# STM32_microcontroller_IOs.net
KiCad netlist of a schematic drawn in Altium Designer
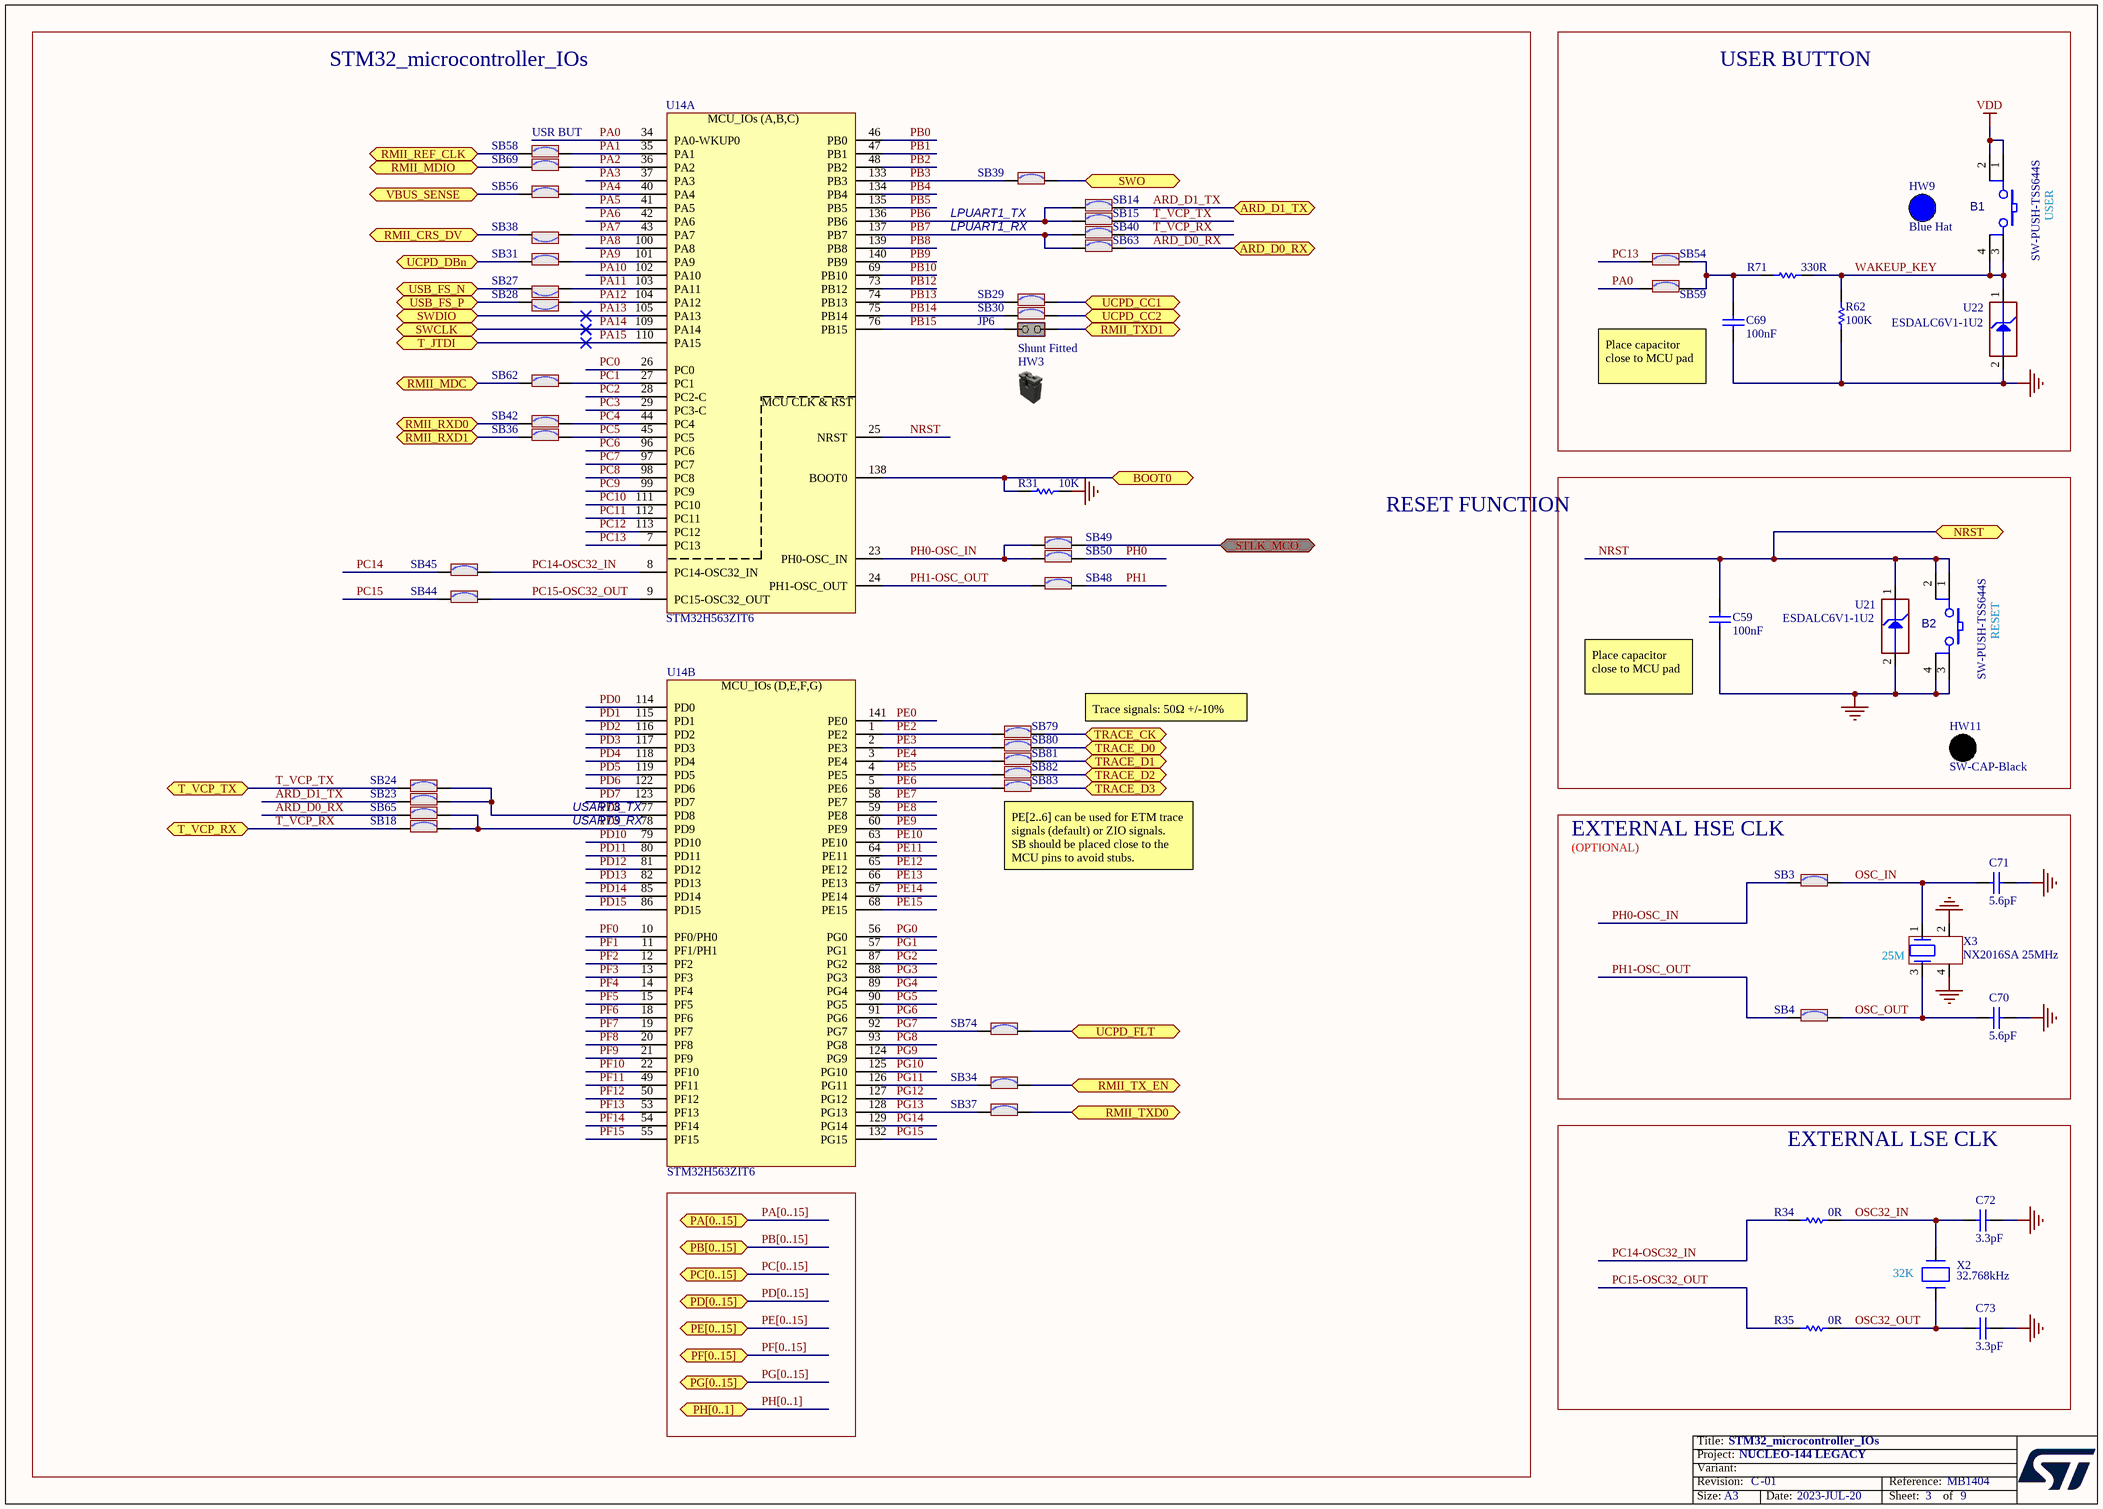
[diagram p0: STM32_microcontroller_IOs.SchDoc]

(export (version "E")
  (design (tool "Eeschema 10.0.6"))
  (components
    (comp (ref "B1")
      (value "SW-PUSH-TSS644S")
      (footprint "MCD_PARTS:SWI_KNITTER_TSS644S")
      (description "Push Button, NO, 0.05A, 12V, 2.6N, SMD, 9.0x6.2mm, T=7.3mm, changeable caps KTSC-6xx")
      (fields
        (field (name "INTERNAL_PART_NUMBER") "MCD-02417")
        (field (name "MANUFACTURER") "KNITTER-SWITCH")
      )
      (libsource (lib "MCD_PARTS_database") (part "SW_PUSH_SMD"))
    )
    (comp (ref "B2")
      (value "SW-PUSH-TSS644S")
      (footprint "MCD_PARTS:SWI_KNITTER_TSS644S")
      (description "Push Button, NO, 0.05A, 12V, 2.6N, SMD, 9.0x6.2mm, T=7.3mm, changeable caps KTSC-6xx")
      (fields
        (field (name "INTERNAL_PART_NUMBER") "MCD-02417")
        (field (name "MANUFACTURER") "KNITTER-SWITCH")
      )
      (libsource (lib "MCD_PARTS_database") (part "SW_PUSH_SMD"))
    )
    (comp (ref "C59")
      (value "100nF")
      (footprint "C0603")
      (description "Capacitor, MLCC, 100nF, 6V3, X5R, +/-10%, 0603, T=0.8mm")
      (fields (field (name "INTERNAL_PART_NUMBER") "MCD-02119") (field (name "MANUFACTURER") "KEMET"))
      (libsource (lib "MCD_PARTS_database") (part "Capacitor"))
    )
    (comp (ref "C69")
      (value "100nF")
      (footprint "C0603")
      (description "Capacitor, MLCC, 100nF, 6V3, X5R, +/-10%, 0603, T=0.8mm")
      (fields (field (name "INTERNAL_PART_NUMBER") "MCD-02119") (field (name "MANUFACTURER") "KEMET"))
      (libsource (lib "MCD_PARTS_database") (part "Capacitor"))
    )
    (comp (ref "C70")
      (value "5.6pF")
      (footprint "MCD_PARTS:C0402")
      (description "Capacitor, MLCC, 5.6pF, 50V, NPO, 5%, 0402, T=0,5mm")
      (fields
        (field (name "INTERNAL_PART_NUMBER") "MCD-01374")
        (field (name "MANUFACTURER_PART_NUMBER") "CC0402BRNPO9BN5R6")
        (field (name "PROVIDED_BY") "SUBCO")
      )
      (libsource (lib "MCD_PARTS_database") (part "Capacitor"))
    )
    (comp (ref "C71")
      (value "5.6pF")
      (footprint "MCD_PARTS:C0402")
      (description "Capacitor, MLCC, 5.6pF, 50V, NPO, 5%, 0402, T=0,5mm")
      (fields
        (field (name "INTERNAL_PART_NUMBER") "MCD-01374")
        (field (name "MANUFACTURER_PART_NUMBER") "CC0402BRNPO9BN5R6")
        (field (name "PROVIDED_BY") "SUBCO")
      )
      (libsource (lib "MCD_PARTS_database") (part "Capacitor"))
    )
    (comp (ref "C72")
      (value "3.3pF")
      (footprint "MCD_PARTS:C0402")
      (description "Capacitor, MLCC, 3.3pF, 50V, NPO, +/-0.1pF, 0402, T=0.5mm")
      (fields (field (name "INTERNAL_PART_NUMBER") "MCD-01775") (field (name "MANUFACTURER") "YAGEO"))
      (libsource (lib "MCD_PARTS_database") (part "Capacitor"))
    )
    (comp (ref "C73")
      (value "3.3pF")
      (footprint "MCD_PARTS:C0402")
      (description "Capacitor, MLCC, 3.3pF, 50V, NPO, +/-0.1pF, 0402, T=0.5mm")
      (fields (field (name "INTERNAL_PART_NUMBER") "MCD-01775") (field (name "MANUFACTURER") "YAGEO"))
      (libsource (lib "MCD_PARTS_database") (part "Capacitor"))
    )
    (comp (ref "HW3")
      (value "Shunt Black 2.54mm")
      (description "SHUNT 2.54mm BLACK")
      (fields
        (field (name "INTERNAL_PART_NUMBER") "MCD-00043")
        (field (name "MANUFACTURER_PART_NUMBER") "SNT-100-BK-G")
        (field (name "PROVIDED_BY") "SUBCO")
      )
      (libsource (lib "MCD_PARTS_database") (part "Shunt Black 2.54mm"))
    )
    (comp (ref "HW9")
      (value "Blue Hat")
      (description "Switch hat, blue, For KTSC-62B")
      (fields (field (name "INTERNAL_PART_NUMBER") "MCD-02136") (field (name "MANUFACTURER") "APEM INC"))
      (libsource (lib "MCD_PARTS_database") (part "BUTTON_HAT_BLUE"))
    )
    (comp (ref "HW11")
      (value "SW-CAP-Black")
      (description "Black round cap for TSS6x series")
      (fields
        (field (name "INTERNAL_PART_NUMBER") "MCD-02420")
        (field (name "MANUFACTURER") "KNITTER-SWITCH")
      )
      (libsource (lib "MCD_PARTS_database") (part "SW-CAP-Black"))
    )
    (comp (ref "JP6")
      (value "Shunt Fitted")
      (footprint "MCD_PARTS:CON_SAMTEC_TSW-102-07-G-S")
      (description "Header, 2x1, 2,54mm, VR, TH, Height 5.84mm/2.54mm - Shunt Fitted by default")
      (fields
        (field (name "INTERNAL_PART_NUMBER") "MCD-00683")
        (field (name "MANUFACTURER_PART_NUMBER") "TSW-102-07-x-S")
        (field (name "PROVIDED_BY") "SUBCO")
      )
      (libsource (lib "MCD_PARTS_database") (part "Jumper_Header 2x1 Fitted"))
    )
    (comp (ref "R31")
      (value "10K")
      (footprint "MCD_PARTS:R0603")
      (description "Resistor,10K,0603,1%,1/10W")
      (fields
        (field (name "INTERNAL_PART_NUMBER") "MCD-00220")
        (field (name "MANUFACTURER_PART_NUMBER") "RC0603FR-0710KL")
        (field (name "PROVIDED_BY") "SUBCO")
      )
      (libsource (lib "MCD_PARTS_database") (part "Resistor"))
    )
    (comp (ref "R34")
      (value "0R")
      (footprint "MCD_PARTS:R0603")
      (description "Resistor,0R,0603,5%,1/10W")
      (fields
        (field (name "INTERNAL_PART_NUMBER") "MCD-00056")
        (field (name "MANUFACTURER_PART_NUMBER") "RC0603JR-070RL")
        (field (name "PROVIDED_BY") "SUBCO")
      )
      (libsource (lib "MCD_PARTS_database") (part "Resistor"))
    )
    (comp (ref "R35")
      (value "0R")
      (footprint "MCD_PARTS:R0603")
      (description "Resistor,0R,0603,5%,1/10W")
      (fields
        (field (name "INTERNAL_PART_NUMBER") "MCD-00056")
        (field (name "MANUFACTURER_PART_NUMBER") "RC0603JR-070RL")
        (field (name "PROVIDED_BY") "SUBCO")
      )
      (libsource (lib "MCD_PARTS_database") (part "Resistor"))
    )
    (comp (ref "R62")
      (value "100K")
      (footprint "MCD_PARTS:R0603")
      (description "Resistor,100K,0603,1%,1/10W")
      (fields
        (field (name "INTERNAL_PART_NUMBER") "MCD-00223")
        (field (name "MANUFACTURER_PART_NUMBER") "RC0603FR-07100KL")
        (field (name "PROVIDED_BY") "SUBCO")
      )
      (libsource (lib "MCD_PARTS_database") (part "Resistor"))
    )
    (comp (ref "R71")
      (value "330R")
      (footprint "MCD_PARTS:R0603")
      (description "Resistor,330R,0603,1%,1/10W")
      (fields
        (field (name "INTERNAL_PART_NUMBER") "MCD-00197")
        (field (name "MANUFACTURER_PART_NUMBER") "RC0603FR-07330RL")
        (field (name "PROVIDED_BY") "SUBCO")
      )
      (libsource (lib "MCD_PARTS_database") (part "Resistor"))
    )
    (comp (ref "SB3")
      (value "SB_ON")
      (footprint "MCD_PARTS:SOLDER-BRIDGE_R0603-0R")
      (description "Solder Bridge ON")
      (fields
        (field (name "INTERNAL_PART_NUMBER") "MCD-00071")
        (field (name "MANUFACTURER_PART_NUMBER") "RC0603JR-070RL")
        (field (name "PROVIDED_BY") "SUBCO")
      )
      (libsource (lib "MCD_PARTS_database") (part "SB_ON"))
    )
    (comp (ref "SB4")
      (value "SB_ON")
      (footprint "MCD_PARTS:SOLDER-BRIDGE_R0603-0R")
      (description "Solder Bridge ON")
      (fields
        (field (name "INTERNAL_PART_NUMBER") "MCD-00071")
        (field (name "MANUFACTURER_PART_NUMBER") "RC0603JR-070RL")
        (field (name "PROVIDED_BY") "SUBCO")
      )
      (libsource (lib "MCD_PARTS_database") (part "SB_ON"))
    )
    (comp (ref "SB14")
      (value "SB_ON")
      (footprint "MCD_PARTS:SOLDER-BRIDGE_R0603-0R")
      (description "Solder Bridge ON")
      (fields
        (field (name "INTERNAL_PART_NUMBER") "MCD-00071")
        (field (name "MANUFACTURER_PART_NUMBER") "RC0603JR-070RL")
        (field (name "PROVIDED_BY") "SUBCO")
      )
      (libsource (lib "") (part "SB_ON_1"))
    )
    (comp (ref "SB15")
      (value "SB_ON")
      (footprint "MCD_PARTS:SOLDER-BRIDGE_R0603-0R")
      (description "Solder Bridge ON")
      (fields
        (field (name "INTERNAL_PART_NUMBER") "MCD-00071")
        (field (name "MANUFACTURER_PART_NUMBER") "RC0603JR-070RL")
        (field (name "PROVIDED_BY") "SUBCO")
      )
      (libsource (lib "") (part "SB_ON_1"))
    )
    (comp (ref "SB18")
      (value "SB_ON")
      (footprint "MCD_PARTS:SOLDER-BRIDGE_R0603-0R")
      (description "Solder Bridge ON")
      (fields
        (field (name "INTERNAL_PART_NUMBER") "MCD-00071")
        (field (name "MANUFACTURER_PART_NUMBER") "RC0603JR-070RL")
        (field (name "PROVIDED_BY") "SUBCO")
      )
      (libsource (lib "") (part "SB_ON_1"))
    )
    (comp (ref "SB23")
      (value "SB_ON")
      (footprint "MCD_PARTS:SOLDER-BRIDGE_R0603-0R")
      (description "Solder Bridge ON")
      (fields
        (field (name "INTERNAL_PART_NUMBER") "MCD-00071")
        (field (name "MANUFACTURER_PART_NUMBER") "RC0603JR-070RL")
        (field (name "PROVIDED_BY") "SUBCO")
      )
      (libsource (lib "") (part "SB_ON_1"))
    )
    (comp (ref "SB24")
      (value "SB_ON")
      (footprint "MCD_PARTS:SOLDER-BRIDGE_R0603-0R")
      (description "Solder Bridge ON")
      (fields
        (field (name "INTERNAL_PART_NUMBER") "MCD-00071")
        (field (name "MANUFACTURER_PART_NUMBER") "RC0603JR-070RL")
        (field (name "PROVIDED_BY") "SUBCO")
      )
      (libsource (lib "") (part "SB_ON_1"))
    )
    (comp (ref "SB27")
      (value "SB_ON")
      (footprint "MCD_PARTS:SOLDER-BRIDGE_R0402-0R")
      (description "Solder Bridge 0402 ON")
      (fields
        (field (name "INTERNAL_PART_NUMBER") "MCD-01618")
        (field (name "MANUFACTURER_PART_NUMBER") "RC0402JR-070RL")
        (field (name "PROVIDED_BY") "SUBCO")
      )
      (libsource (lib "") (part "SB_ON_2"))
    )
    (comp (ref "SB28")
      (value "SB_ON")
      (footprint "MCD_PARTS:SOLDER-BRIDGE_R0402-0R")
      (description "Solder Bridge 0402 ON")
      (fields
        (field (name "INTERNAL_PART_NUMBER") "MCD-01618")
        (field (name "MANUFACTURER_PART_NUMBER") "RC0402JR-070RL")
        (field (name "PROVIDED_BY") "SUBCO")
      )
      (libsource (lib "") (part "SB_ON_2"))
    )
    (comp (ref "SB29")
      (value "SB_ON")
      (footprint "MCD_PARTS:SOLDER-BRIDGE_R0603-0R")
      (description "Solder Bridge ON")
      (fields
        (field (name "INTERNAL_PART_NUMBER") "MCD-00071")
        (field (name "MANUFACTURER_PART_NUMBER") "RC0603JR-070RL")
        (field (name "PROVIDED_BY") "SUBCO")
      )
      (libsource (lib "MCD_PARTS_database") (part "SB_ON"))
    )
    (comp (ref "SB30")
      (value "SB_ON")
      (footprint "MCD_PARTS:SOLDER-BRIDGE_R0603-0R")
      (description "Solder Bridge ON")
      (fields
        (field (name "INTERNAL_PART_NUMBER") "MCD-00071")
        (field (name "MANUFACTURER_PART_NUMBER") "RC0603JR-070RL")
        (field (name "PROVIDED_BY") "SUBCO")
      )
      (libsource (lib "MCD_PARTS_database") (part "SB_ON"))
    )
    (comp (ref "SB31")
      (value "SB_ON")
      (footprint "MCD_PARTS:SOLDER-BRIDGE_R0402-0R")
      (description "Solder Bridge 0402 ON")
      (fields
        (field (name "INTERNAL_PART_NUMBER") "MCD-01618")
        (field (name "MANUFACTURER_PART_NUMBER") "RC0402JR-070RL")
        (field (name "PROVIDED_BY") "SUBCO")
      )
      (libsource (lib "MCD_PARTS_database") (part "SB_ON"))
    )
    (comp (ref "SB34")
      (value "SB_ON")
      (footprint "MCD_PARTS:SOLDER-BRIDGE_R0603-0R")
      (description "Solder Bridge ON")
      (fields
        (field (name "INTERNAL_PART_NUMBER") "MCD-00071")
        (field (name "MANUFACTURER_PART_NUMBER") "RC0603JR-070RL")
        (field (name "PROVIDED_BY") "SUBCO")
      )
      (libsource (lib "") (part "SB_ON_1"))
    )
    (comp (ref "SB36")
      (value "SB_ON")
      (footprint "MCD_PARTS:SOLDER-BRIDGE_R0402-0R")
      (description "Solder Bridge 0402 ON")
      (fields
        (field (name "INTERNAL_PART_NUMBER") "MCD-01618")
        (field (name "MANUFACTURER_PART_NUMBER") "RC0402JR-070RL")
        (field (name "PROVIDED_BY") "SUBCO")
      )
      (libsource (lib "MCD_PARTS_database") (part "SB_ON"))
    )
    (comp (ref "SB37")
      (value "SB_ON")
      (footprint "MCD_PARTS:SOLDER-BRIDGE_R0603-0R")
      (description "Solder Bridge ON")
      (fields
        (field (name "INTERNAL_PART_NUMBER") "MCD-00071")
        (field (name "MANUFACTURER_PART_NUMBER") "RC0603JR-070RL")
        (field (name "PROVIDED_BY") "SUBCO")
      )
      (libsource (lib "") (part "SB_ON_1"))
    )
    (comp (ref "SB38")
      (value "SB_ON")
      (footprint "MCD_PARTS:SOLDER-BRIDGE_R0402-0R")
      (description "Solder Bridge 0402 ON")
      (fields
        (field (name "INTERNAL_PART_NUMBER") "MCD-01618")
        (field (name "MANUFACTURER_PART_NUMBER") "RC0402JR-070RL")
        (field (name "PROVIDED_BY") "SUBCO")
      )
      (libsource (lib "") (part "SB_ON_2"))
    )
    (comp (ref "SB39")
      (value "SB_ON")
      (footprint "MCD_PARTS:SOLDER-BRIDGE_R0603-0R")
      (description "Solder Bridge ON")
      (fields
        (field (name "INTERNAL_PART_NUMBER") "MCD-00071")
        (field (name "MANUFACTURER_PART_NUMBER") "RC0603JR-070RL")
        (field (name "PROVIDED_BY") "SUBCO")
      )
      (libsource (lib "") (part "SB_ON_1"))
    )
    (comp (ref "SB40")
      (value "SB_ON")
      (footprint "MCD_PARTS:SOLDER-BRIDGE_R0603-0R")
      (description "Solder Bridge ON")
      (fields
        (field (name "INTERNAL_PART_NUMBER") "MCD-00071")
        (field (name "MANUFACTURER_PART_NUMBER") "RC0603JR-070RL")
        (field (name "PROVIDED_BY") "SUBCO")
      )
      (libsource (lib "") (part "SB_ON_1"))
    )
    (comp (ref "SB42")
      (value "SB_ON")
      (footprint "MCD_PARTS:SOLDER-BRIDGE_R0603-0R")
      (description "Solder Bridge ON")
      (fields
        (field (name "INTERNAL_PART_NUMBER") "MCD-00071")
        (field (name "MANUFACTURER_PART_NUMBER") "RC0603JR-070RL")
        (field (name "PROVIDED_BY") "SUBCO")
      )
      (libsource (lib "MCD_PARTS_database") (part "SB_ON"))
    )
    (comp (ref "SB44")
      (value "SB_ON")
      (footprint "MCD_PARTS:SOLDER-BRIDGE_R0402-0R")
      (description "Solder Bridge 0402 ON")
      (fields
        (field (name "INTERNAL_PART_NUMBER") "MCD-01618")
        (field (name "MANUFACTURER_PART_NUMBER") "RC0402JR-070RL")
        (field (name "PROVIDED_BY") "SUBCO")
      )
      (libsource (lib "MCD_PARTS_database") (part "SB_ON"))
    )
    (comp (ref "SB45")
      (value "SB_ON")
      (footprint "MCD_PARTS:SOLDER-BRIDGE_R0402-0R")
      (description "Solder Bridge 0402 ON")
      (fields
        (field (name "INTERNAL_PART_NUMBER") "MCD-01618")
        (field (name "MANUFACTURER_PART_NUMBER") "RC0402JR-070RL")
        (field (name "PROVIDED_BY") "SUBCO")
      )
      (libsource (lib "MCD_PARTS_database") (part "SB_ON"))
    )
    (comp (ref "SB48")
      (value "SB_ON")
      (footprint "MCD_PARTS:SOLDER-BRIDGE_R0603-0R")
      (description "Solder Bridge ON")
      (fields
        (field (name "INTERNAL_PART_NUMBER") "MCD-00071")
        (field (name "MANUFACTURER_PART_NUMBER") "RC0603JR-070RL")
        (field (name "PROVIDED_BY") "SUBCO")
      )
      (libsource (lib "MCD_PARTS_database") (part "SB_ON"))
    )
    (comp (ref "SB49")
      (value "SB_ON")
      (footprint "MCD_PARTS:SOLDER-BRIDGE_R0603-0R")
      (description "Solder Bridge ON")
      (fields
        (field (name "INTERNAL_PART_NUMBER") "MCD-00071")
        (field (name "MANUFACTURER_PART_NUMBER") "RC0603JR-070RL")
        (field (name "PROVIDED_BY") "SUBCO")
      )
      (libsource (lib "MCD_PARTS_database") (part "SB_ON"))
    )
    (comp (ref "SB50")
      (value "SB_ON")
      (footprint "MCD_PARTS:SOLDER-BRIDGE_R0603-0R")
      (description "Solder Bridge ON")
      (fields
        (field (name "INTERNAL_PART_NUMBER") "MCD-00071")
        (field (name "MANUFACTURER_PART_NUMBER") "RC0603JR-070RL")
        (field (name "PROVIDED_BY") "SUBCO")
      )
      (libsource (lib "MCD_PARTS_database") (part "SB_ON"))
    )
    (comp (ref "SB54")
      (value "SB_ON")
      (footprint "MCD_PARTS:SOLDER-BRIDGE_R0402-0R")
      (description "Solder Bridge 0402 ON")
      (fields
        (field (name "INTERNAL_PART_NUMBER") "MCD-01618")
        (field (name "MANUFACTURER_PART_NUMBER") "RC0402JR-070RL")
        (field (name "PROVIDED_BY") "SUBCO")
      )
      (libsource (lib "MCD_PARTS_database") (part "SB_ON"))
    )
    (comp (ref "SB56")
      (value "SB_ON")
      (footprint "MCD_PARTS:SOLDER-BRIDGE_R0402-0R")
      (description "Solder Bridge 0402 ON")
      (fields
        (field (name "INTERNAL_PART_NUMBER") "MCD-01618")
        (field (name "MANUFACTURER_PART_NUMBER") "RC0402JR-070RL")
        (field (name "PROVIDED_BY") "SUBCO")
      )
      (libsource (lib "MCD_PARTS_database") (part "SB_ON"))
    )
    (comp (ref "SB58")
      (value "SB_ON")
      (footprint "MCD_PARTS:SOLDER-BRIDGE_R0603-0R")
      (description "Solder Bridge ON")
      (fields
        (field (name "INTERNAL_PART_NUMBER") "MCD-00071")
        (field (name "MANUFACTURER_PART_NUMBER") "RC0603JR-070RL")
        (field (name "PROVIDED_BY") "SUBCO")
      )
      (libsource (lib "") (part "SB_ON_1"))
    )
    (comp (ref "SB59")
      (value "SB_ON")
      (footprint "MCD_PARTS:SOLDER-BRIDGE_R0603-0R")
      (description "Solder Bridge ON")
      (fields
        (field (name "INTERNAL_PART_NUMBER") "MCD-00071")
        (field (name "MANUFACTURER_PART_NUMBER") "RC0603JR-070RL")
        (field (name "PROVIDED_BY") "SUBCO")
      )
      (libsource (lib "") (part "SB_ON_1"))
    )
    (comp (ref "SB62")
      (value "SB_ON")
      (footprint "MCD_PARTS:SOLDER-BRIDGE_R0603-0R")
      (description "Solder Bridge ON")
      (fields
        (field (name "INTERNAL_PART_NUMBER") "MCD-00071")
        (field (name "MANUFACTURER_PART_NUMBER") "RC0603JR-070RL")
        (field (name "PROVIDED_BY") "SUBCO")
      )
      (libsource (lib "MCD_PARTS_database") (part "SB_ON"))
    )
    (comp (ref "SB63")
      (value "SB_ON")
      (footprint "MCD_PARTS:SOLDER-BRIDGE_R0402-0R")
      (description "Solder Bridge 0402 ON")
      (fields
        (field (name "INTERNAL_PART_NUMBER") "MCD-01618")
        (field (name "MANUFACTURER_PART_NUMBER") "RC0402JR-070RL")
        (field (name "PROVIDED_BY") "SUBCO")
      )
      (libsource (lib "MCD_PARTS_database") (part "SB_ON"))
    )
    (comp (ref "SB65")
      (value "SB_ON")
      (footprint "MCD_PARTS:SOLDER-BRIDGE_R0402-0R")
      (description "Solder Bridge 0402 ON")
      (fields
        (field (name "INTERNAL_PART_NUMBER") "MCD-01618")
        (field (name "MANUFACTURER_PART_NUMBER") "RC0402JR-070RL")
        (field (name "PROVIDED_BY") "SUBCO")
      )
      (libsource (lib "MCD_PARTS_database") (part "SB_ON"))
    )
    (comp (ref "SB69")
      (value "SB_ON")
      (footprint "MCD_PARTS:SOLDER-BRIDGE_R0603-0R")
      (description "Solder Bridge ON")
      (fields
        (field (name "INTERNAL_PART_NUMBER") "MCD-00071")
        (field (name "MANUFACTURER_PART_NUMBER") "RC0603JR-070RL")
        (field (name "PROVIDED_BY") "SUBCO")
      )
      (libsource (lib "") (part "SB_ON_1"))
    )
    (comp (ref "SB74")
      (value "SB_ON")
      (footprint "MCD_PARTS:SOLDER-BRIDGE_R0603-0R")
      (description "Solder Bridge ON")
      (fields
        (field (name "INTERNAL_PART_NUMBER") "MCD-00071")
        (field (name "MANUFACTURER_PART_NUMBER") "RC0603JR-070RL")
        (field (name "PROVIDED_BY") "SUBCO")
      )
      (libsource (lib "") (part "SB_ON_1"))
    )
    (comp (ref "SB79")
      (value "SB_ON")
      (footprint "MCD_PARTS:SOLDER-BRIDGE_R0402-0R")
      (description "Solder Bridge 0402 ON")
      (fields
        (field (name "INTERNAL_PART_NUMBER") "MCD-01618")
        (field (name "MANUFACTURER_PART_NUMBER") "RC0402JR-070RL")
        (field (name "PROVIDED_BY") "SUBCO")
      )
      (libsource (lib "MCD_PARTS_database") (part "SB_ON"))
    )
    (comp (ref "SB80")
      (value "SB_ON")
      (footprint "MCD_PARTS:SOLDER-BRIDGE_R0402-0R")
      (description "Solder Bridge 0402 ON")
      (fields
        (field (name "INTERNAL_PART_NUMBER") "MCD-01618")
        (field (name "MANUFACTURER_PART_NUMBER") "RC0402JR-070RL")
        (field (name "PROVIDED_BY") "SUBCO")
      )
      (libsource (lib "MCD_PARTS_database") (part "SB_ON"))
    )
    (comp (ref "SB81")
      (value "SB_ON")
      (footprint "MCD_PARTS:SOLDER-BRIDGE_R0402-0R")
      (description "Solder Bridge 0402 ON")
      (fields
        (field (name "INTERNAL_PART_NUMBER") "MCD-01618")
        (field (name "MANUFACTURER_PART_NUMBER") "RC0402JR-070RL")
        (field (name "PROVIDED_BY") "SUBCO")
      )
      (libsource (lib "MCD_PARTS_database") (part "SB_ON"))
    )
    (comp (ref "SB82")
      (value "SB_ON")
      (footprint "MCD_PARTS:SOLDER-BRIDGE_R0402-0R")
      (description "Solder Bridge 0402 ON")
      (fields
        (field (name "INTERNAL_PART_NUMBER") "MCD-01618")
        (field (name "MANUFACTURER_PART_NUMBER") "RC0402JR-070RL")
        (field (name "PROVIDED_BY") "SUBCO")
      )
      (libsource (lib "MCD_PARTS_database") (part "SB_ON"))
    )
    (comp (ref "SB83")
      (value "SB_ON")
      (footprint "MCD_PARTS:SOLDER-BRIDGE_R0402-0R")
      (description "Solder Bridge 0402 ON")
      (fields
        (field (name "INTERNAL_PART_NUMBER") "MCD-01618")
        (field (name "MANUFACTURER_PART_NUMBER") "RC0402JR-070RL")
        (field (name "PROVIDED_BY") "SUBCO")
      )
      (libsource (lib "MCD_PARTS_database") (part "SB_ON"))
    )
    (comp (ref "U14")
      (value "STM32H563ZIT6")
      (footprint "MCD_PARTS:ICC_LQFP144_20X20_P050_SOCKET_YAMAICHI_IC149-144-145-B5_NM")
      (description "STM32H563ZIT6, LQFP144 package, 20x20")
      (fields
        (field (name "INTERNAL_PART_NUMBER") "MCD-02359")
        (field (name "MANUFACTURER") "STMICROELECTRONICS")
      )
      (libsource (lib "MCD_PARTS_database") (part "STM32H563ZIT6"))
    )
    (comp (ref "U21")
      (value "ESDALC6V1-1U2")
      (footprint "MCD_PARTS:ESD_ST0201")
      (description "ESD protection 6V1")
      (fields
        (field (name "INTERNAL_PART_NUMBER") "MCD-00170")
        (field (name "MANUFACTURER") "STMICROELECTRONICS")
        (field (name "PROVIDED_BY") "SUBCO with ST control")
      )
      (libsource (lib "MCD_PARTS_database") (part "ESD-TRANSIL"))
    )
    (comp (ref "U22")
      (value "ESDALC6V1-1U2")
      (footprint "MCD_PARTS:ESD_ST0201")
      (description "ESD protection 6V1")
      (fields
        (field (name "INTERNAL_PART_NUMBER") "MCD-00170")
        (field (name "MANUFACTURER") "STMICROELECTRONICS")
        (field (name "PROVIDED_BY") "SUBCO with ST control")
      )
      (libsource (lib "MCD_PARTS_database") (part "ESD-TRANSIL"))
    )
    (comp (ref "X2")
      (value "32.768kHz")
      (footprint "MCD_PARTS:CRY_NX1610SE_2P")
      (description "Crystal, 32.768kHz, 9pF, +/-20ppm, 70KR, 1.6x1mm")
      (fields (field (name "INTERNAL_PART_NUMBER") "MCD-02291") (field (name "MANUFACTURER") "NDK"))
      (libsource (lib "MCD_PARTS_database") (part "XTAL_2_PINS"))
    )
    (comp (ref "X3")
      (value "NX2016SA 25MHz")
      (footprint "MCD_PARTS:CRY_NX2016SA_4P")
      (description "Crystal 25MHz, 6pF, +-20ppm, 80ohms max, SMD")
      (fields
        (field (name "INTERNAL_PART_NUMBER") "MCD-01364")
        (field (name "MANUFACTURER_PART_NUMBER") "NX2016SA 25MHz EXS00A-CS11321")
        (field (name "PROVIDED_BY") "SUBCO")
      )
      (libsource (lib "MCD_PARTS_database") (part "XTAL_4_PINS"))
    )
  )
  (nets
    (net (code "3") (name "/ARD_D0_RX") (class "Default")
      (node (ref "SB63") (pin "2") (pinfunction "2_2") (pintype "passive"))
      (node (ref "SB65") (pin "1") (pinfunction "1_1") (pintype "passive"))
    )
    (net (code "4") (name "/ARD_D1_TX") (class "Default")
      (node (ref "SB14") (pin "1") (pinfunction "1_1") (pintype "passive"))
      (node (ref "SB23") (pin "2") (pinfunction "2_2") (pintype "passive"))
    )
    (net (code "5") (name "/BOOT0") (class "Default")
      (node (ref "R31") (pin "1") (pinfunction "1_1") (pintype "passive"))
      (node (ref "U14") (pin "138") (pinfunction "BOOT0_138") (pintype "passive"))
    )
    (net (code "6") (name "/NRST") (class "Default")
      (node (ref "B2") (pin "1") (pinfunction "1_1") (pintype "passive"))
      (node (ref "B2") (pin "2") (pinfunction "2_2") (pintype "passive"))
      (node (ref "C59") (pin "2") (pinfunction "2_2") (pintype "passive"))
      (node (ref "U14") (pin "25") (pinfunction "NRST_25") (pintype "passive"))
      (node (ref "U21") (pin "1") (pinfunction "IO1_1") (pintype "passive"))
    )
    (net (code "7") (name "/OSC32_IN") (class "Default")
      (node (ref "C72") (pin "1") (pinfunction "1_1") (pintype "passive"))
      (node (ref "R34") (pin "2") (pinfunction "2_2") (pintype "passive"))
      (node (ref "X2") (pin "2") (pinfunction "X2_2") (pintype "passive"))
    )
    (net (code "8") (name "/OSC32_OUT") (class "Default")
      (node (ref "C73") (pin "1") (pinfunction "1_1") (pintype "passive"))
      (node (ref "R35") (pin "2") (pinfunction "2_2") (pintype "passive"))
      (node (ref "X2") (pin "1") (pinfunction "X1_1") (pintype "passive"))
    )
    (net (code "9") (name "/OSC_IN") (class "Default")
      (node (ref "C71") (pin "1") (pinfunction "1_1") (pintype "passive"))
      (node (ref "SB3") (pin "2") (pinfunction "2_2") (pintype "passive"))
      (node (ref "X3") (pin "1") (pinfunction "1_1") (pintype "passive"))
    )
    (net (code "10") (name "/OSC_OUT") (class "Default")
      (node (ref "C70") (pin "1") (pinfunction "1_1") (pintype "passive"))
      (node (ref "SB4") (pin "2") (pinfunction "2_2") (pintype "passive"))
      (node (ref "X3") (pin "3") (pinfunction "3_3") (pintype "passive"))
    )
    (net (code "11") (name "/PA0") (class "Default")
      (node (ref "SB59") (pin "2") (pinfunction "2_2") (pintype "passive"))
      (node (ref "U14") (pin "34") (pinfunction "PA0-WKUP0_34") (pintype "passive"))
    )
    (net (code "12") (name "/PA1") (class "Default")
      (node (ref "SB58") (pin "1") (pinfunction "1_1") (pintype "passive"))
      (node (ref "U14") (pin "35") (pinfunction "PA1_35") (pintype "passive"))
    )
    (net (code "13") (name "/PA2") (class "Default")
      (node (ref "SB69") (pin "1") (pinfunction "1_1") (pintype "passive"))
      (node (ref "U14") (pin "36") (pinfunction "PA2_36") (pintype "passive"))
    )
    (net (code "14") (name "/PA3") (class "Default")
      (node (ref "U14") (pin "37") (pinfunction "PA3_37") (pintype "passive"))
    )
    (net (code "15") (name "/PA4") (class "Default")
      (node (ref "SB56") (pin "2") (pinfunction "2_2") (pintype "passive"))
      (node (ref "U14") (pin "40") (pinfunction "PA4_40") (pintype "passive"))
    )
    (net (code "16") (name "/PA5") (class "Default")
      (node (ref "U14") (pin "41") (pinfunction "PA5_41") (pintype "passive"))
    )
    (net (code "17") (name "/PA6") (class "Default")
      (node (ref "U14") (pin "42") (pinfunction "PA6_42") (pintype "passive"))
    )
    (net (code "18") (name "/PA7") (class "Default")
      (node (ref "SB38") (pin "1") (pinfunction "1_1") (pintype "passive"))
      (node (ref "U14") (pin "43") (pinfunction "PA7_43") (pintype "passive"))
    )
    (net (code "19") (name "/PA8") (class "Default")
      (node (ref "U14") (pin "100") (pinfunction "PA8_100") (pintype "passive"))
    )
    (net (code "20") (name "/PA9") (class "Default")
      (node (ref "SB31") (pin "2") (pinfunction "2_2") (pintype "passive"))
      (node (ref "U14") (pin "101") (pinfunction "PA9_101") (pintype "passive"))
    )
    (net (code "21") (name "/PA10") (class "Default")
      (node (ref "U14") (pin "102") (pinfunction "PA10_102") (pintype "passive"))
    )
    (net (code "22") (name "/PA11") (class "Default")
      (node (ref "SB27") (pin "1") (pinfunction "1_1") (pintype "passive"))
      (node (ref "U14") (pin "103") (pinfunction "PA11_103") (pintype "passive"))
    )
    (net (code "23") (name "/PA12") (class "Default")
      (node (ref "SB28") (pin "1") (pinfunction "1_1") (pintype "passive"))
      (node (ref "U14") (pin "104") (pinfunction "PA12_104") (pintype "passive"))
    )
    (net (code "24") (name "/PA13") (class "Default")
      (node (ref "U14") (pin "105") (pinfunction "PA13_105") (pintype "passive"))
    )
    (net (code "25") (name "/PA14") (class "Default")
      (node (ref "U14") (pin "109") (pinfunction "PA14_109") (pintype "passive"))
    )
    (net (code "26") (name "/PA15") (class "Default")
      (node (ref "U14") (pin "110") (pinfunction "PA15_110") (pintype "passive"))
    )
    (net (code "28") (name "/PB0") (class "Default")
      (node (ref "U14") (pin "46") (pinfunction "PB0_46") (pintype "passive"))
    )
    (net (code "29") (name "/PB1") (class "Default")
      (node (ref "U14") (pin "47") (pinfunction "PB1_47") (pintype "passive"))
    )
    (net (code "30") (name "/PB2") (class "Default")
      (node (ref "U14") (pin "48") (pinfunction "PB2_48") (pintype "passive"))
    )
    (net (code "31") (name "/PB3") (class "Default")
      (node (ref "SB39") (pin "2") (pinfunction "2_2") (pintype "passive"))
      (node (ref "U14") (pin "133") (pinfunction "PB3_133") (pintype "passive"))
    )
    (net (code "32") (name "/PB4") (class "Default")
      (node (ref "U14") (pin "134") (pinfunction "PB4_134") (pintype "passive"))
    )
    (net (code "33") (name "/PB5") (class "Default")
      (node (ref "U14") (pin "135") (pinfunction "PB5_135") (pintype "passive"))
    )
    (net (code "34") (name "/PB6") (class "Default")
      (node (ref "SB14") (pin "2") (pinfunction "2_2") (pintype "passive"))
      (node (ref "SB15") (pin "2") (pinfunction "2_2") (pintype "passive"))
      (node (ref "U14") (pin "136") (pinfunction "PB6_136") (pintype "passive"))
    )
    (net (code "35") (name "/PB7") (class "Default")
      (node (ref "SB40") (pin "2") (pinfunction "2_2") (pintype "passive"))
      (node (ref "SB63") (pin "1") (pinfunction "1_1") (pintype "passive"))
      (node (ref "U14") (pin "137") (pinfunction "PB7_137") (pintype "passive"))
    )
    (net (code "36") (name "/PB8") (class "Default")
      (node (ref "U14") (pin "139") (pinfunction "PB8_139") (pintype "passive"))
    )
    (net (code "37") (name "/PB9") (class "Default")
      (node (ref "U14") (pin "140") (pinfunction "PB9_140") (pintype "passive"))
    )
    (net (code "38") (name "/PB10") (class "Default")
      (node (ref "U14") (pin "69") (pinfunction "PB10_69") (pintype "passive"))
    )
    (net (code "39") (name "/PB12") (class "Default")
      (node (ref "U14") (pin "73") (pinfunction "PB12_73") (pintype "passive"))
    )
    (net (code "40") (name "/PB13") (class "Default")
      (node (ref "SB29") (pin "1") (pinfunction "1_1") (pintype "passive"))
      (node (ref "U14") (pin "74") (pinfunction "PB13_74") (pintype "passive"))
    )
    (net (code "41") (name "/PB14") (class "Default")
      (node (ref "SB30") (pin "1") (pinfunction "1_1") (pintype "passive"))
      (node (ref "U14") (pin "75") (pinfunction "PB14_75") (pintype "passive"))
    )
    (net (code "42") (name "/PB15") (class "Default")
      (node (ref "JP6") (pin "1") (pinfunction "COMMON_1") (pintype "passive"))
      (node (ref "U14") (pin "76") (pinfunction "PB15_76") (pintype "passive"))
    )
    (net (code "44") (name "/PC0") (class "Default")
      (node (ref "U14") (pin "26") (pinfunction "PC0_26") (pintype "passive"))
    )
    (net (code "45") (name "/PC1") (class "Default")
      (node (ref "SB62") (pin "2") (pinfunction "2_2") (pintype "passive"))
      (node (ref "U14") (pin "27") (pinfunction "PC1_27") (pintype "passive"))
    )
    (net (code "46") (name "/PC2") (class "Default")
      (node (ref "U14") (pin "28") (pinfunction "PC2-C_28") (pintype "passive"))
    )
    (net (code "47") (name "/PC3") (class "Default")
      (node (ref "U14") (pin "29") (pinfunction "PC3-C_29") (pintype "passive"))
    )
    (net (code "48") (name "/PC4") (class "Default")
      (node (ref "SB42") (pin "2") (pinfunction "2_2") (pintype "passive"))
      (node (ref "U14") (pin "44") (pinfunction "PC4_44") (pintype "passive"))
    )
    (net (code "49") (name "/PC5") (class "Default")
      (node (ref "SB36") (pin "2") (pinfunction "2_2") (pintype "passive"))
      (node (ref "U14") (pin "45") (pinfunction "PC5_45") (pintype "passive"))
    )
    (net (code "50") (name "/PC6") (class "Default")
      (node (ref "U14") (pin "96") (pinfunction "PC6_96") (pintype "passive"))
    )
    (net (code "51") (name "/PC7") (class "Default")
      (node (ref "U14") (pin "97") (pinfunction "PC7_97") (pintype "passive"))
    )
    (net (code "52") (name "/PC8") (class "Default")
      (node (ref "U14") (pin "98") (pinfunction "PC8_98") (pintype "passive"))
    )
    (net (code "53") (name "/PC9") (class "Default")
      (node (ref "U14") (pin "99") (pinfunction "PC9_99") (pintype "passive"))
    )
    (net (code "54") (name "/PC10") (class "Default")
      (node (ref "U14") (pin "111") (pinfunction "PC10_111") (pintype "passive"))
    )
    (net (code "55") (name "/PC11") (class "Default")
      (node (ref "U14") (pin "112") (pinfunction "PC11_112") (pintype "passive"))
    )
    (net (code "56") (name "/PC12") (class "Default")
      (node (ref "U14") (pin "113") (pinfunction "PC12_113") (pintype "passive"))
    )
    (net (code "57") (name "/PC13") (class "Default")
      (node (ref "SB54") (pin "1") (pinfunction "1_1") (pintype "passive"))
      (node (ref "U14") (pin "7") (pinfunction "PC13_7") (pintype "passive"))
    )
    (net (code "58") (name "/PC14") (class "Default")
      (node (ref "SB45") (pin "1") (pinfunction "1_1") (pintype "passive"))
    )
    (net (code "59") (name "/PC14-OSC32_IN") (class "Default")
      (node (ref "R34") (pin "1") (pinfunction "1_1") (pintype "passive"))
      (node (ref "SB45") (pin "2") (pinfunction "2_2") (pintype "passive"))
      (node (ref "U14") (pin "8") (pinfunction "PC14-OSC32_IN_8") (pintype "passive"))
    )
    (net (code "60") (name "/PC15") (class "Default")
      (node (ref "SB44") (pin "1") (pinfunction "1_1") (pintype "passive"))
    )
    (net (code "61") (name "/PC15-OSC32_OUT") (class "Default")
      (node (ref "R35") (pin "1") (pinfunction "1_1") (pintype "passive"))
      (node (ref "SB44") (pin "2") (pinfunction "2_2") (pintype "passive"))
      (node (ref "U14") (pin "9") (pinfunction "PC15-OSC32_OUT_9") (pintype "passive"))
    )
    (net (code "63") (name "/PD0") (class "Default")
      (node (ref "U14") (pin "114") (pinfunction "PD0_114") (pintype "passive"))
    )
    (net (code "64") (name "/PD1") (class "Default")
      (node (ref "U14") (pin "115") (pinfunction "PD1_115") (pintype "passive"))
    )
    (net (code "65") (name "/PD2") (class "Default")
      (node (ref "U14") (pin "116") (pinfunction "PD2_116") (pintype "passive"))
    )
    (net (code "66") (name "/PD3") (class "Default")
      (node (ref "U14") (pin "117") (pinfunction "PD3_117") (pintype "passive"))
    )
    (net (code "67") (name "/PD4") (class "Default")
      (node (ref "U14") (pin "118") (pinfunction "PD4_118") (pintype "passive"))
    )
    (net (code "68") (name "/PD5") (class "Default")
      (node (ref "U14") (pin "119") (pinfunction "PD5_119") (pintype "passive"))
    )
    (net (code "69") (name "/PD6") (class "Default")
      (node (ref "U14") (pin "122") (pinfunction "PD6_122") (pintype "passive"))
    )
    (net (code "70") (name "/PD7") (class "Default")
      (node (ref "U14") (pin "123") (pinfunction "PD7_123") (pintype "passive"))
    )
    (net (code "71") (name "/PD8") (class "Default")
      (node (ref "SB23") (pin "1") (pinfunction "1_1") (pintype "passive"))
      (node (ref "SB24") (pin "1") (pinfunction "1_1") (pintype "passive"))
      (node (ref "U14") (pin "77") (pinfunction "PD8_77") (pintype "passive"))
    )
    (net (code "72") (name "/PD9") (class "Default")
      (node (ref "SB18") (pin "1") (pinfunction "1_1") (pintype "passive"))
      (node (ref "SB65") (pin "2") (pinfunction "2_2") (pintype "passive"))
      (node (ref "U14") (pin "78") (pinfunction "PD9_78") (pintype "passive"))
    )
    (net (code "73") (name "/PD10") (class "Default")
      (node (ref "U14") (pin "79") (pinfunction "PD10_79") (pintype "passive"))
    )
    (net (code "74") (name "/PD11") (class "Default")
      (node (ref "U14") (pin "80") (pinfunction "PD11_80") (pintype "passive"))
    )
    (net (code "75") (name "/PD12") (class "Default")
      (node (ref "U14") (pin "81") (pinfunction "PD12_81") (pintype "passive"))
    )
    (net (code "76") (name "/PD13") (class "Default")
      (node (ref "U14") (pin "82") (pinfunction "PD13_82") (pintype "passive"))
    )
    (net (code "77") (name "/PD14") (class "Default")
      (node (ref "U14") (pin "85") (pinfunction "PD14_85") (pintype "passive"))
    )
    (net (code "78") (name "/PD15") (class "Default")
      (node (ref "U14") (pin "86") (pinfunction "PD15_86") (pintype "passive"))
    )
    (net (code "80") (name "/PE0") (class "Default")
      (node (ref "U14") (pin "141") (pinfunction "PE0_141") (pintype "passive"))
    )
    (net (code "81") (name "/PE2") (class "Default")
      (node (ref "SB79") (pin "1") (pinfunction "1_1") (pintype "passive"))
      (node (ref "U14") (pin "1") (pinfunction "PE2_1") (pintype "passive"))
    )
    (net (code "82") (name "/PE3") (class "Default")
      (node (ref "SB80") (pin "1") (pinfunction "1_1") (pintype "passive"))
      (node (ref "U14") (pin "2") (pinfunction "PE3_2") (pintype "passive"))
    )
    (net (code "83") (name "/PE4") (class "Default")
      (node (ref "SB81") (pin "1") (pinfunction "1_1") (pintype "passive"))
      (node (ref "U14") (pin "3") (pinfunction "PE4_3") (pintype "passive"))
    )
    (net (code "84") (name "/PE5") (class "Default")
      (node (ref "SB82") (pin "1") (pinfunction "1_1") (pintype "passive"))
      (node (ref "U14") (pin "4") (pinfunction "PE5_4") (pintype "passive"))
    )
    (net (code "85") (name "/PE6") (class "Default")
      (node (ref "SB83") (pin "1") (pinfunction "1_1") (pintype "passive"))
      (node (ref "U14") (pin "5") (pinfunction "PE6_5") (pintype "passive"))
    )
    (net (code "86") (name "/PE7") (class "Default")
      (node (ref "U14") (pin "58") (pinfunction "PE7_58") (pintype "passive"))
    )
    (net (code "87") (name "/PE8") (class "Default")
      (node (ref "U14") (pin "59") (pinfunction "PE8_59") (pintype "passive"))
    )
    (net (code "88") (name "/PE9") (class "Default")
      (node (ref "U14") (pin "60") (pinfunction "PE9_60") (pintype "passive"))
    )
    (net (code "89") (name "/PE10") (class "Default")
      (node (ref "U14") (pin "63") (pinfunction "PE10_63") (pintype "passive"))
    )
    (net (code "90") (name "/PE11") (class "Default")
      (node (ref "U14") (pin "64") (pinfunction "PE11_64") (pintype "passive"))
    )
    (net (code "91") (name "/PE12") (class "Default")
      (node (ref "U14") (pin "65") (pinfunction "PE12_65") (pintype "passive"))
    )
    (net (code "92") (name "/PE13") (class "Default")
      (node (ref "U14") (pin "66") (pinfunction "PE13_66") (pintype "passive"))
    )
    (net (code "93") (name "/PE14") (class "Default")
      (node (ref "U14") (pin "67") (pinfunction "PE14_67") (pintype "passive"))
    )
    (net (code "94") (name "/PE15") (class "Default")
      (node (ref "U14") (pin "68") (pinfunction "PE15_68") (pintype "passive"))
    )
    (net (code "96") (name "/PF0") (class "Default")
      (node (ref "U14") (pin "10") (pinfunction "PF0/PH0_10") (pintype "passive"))
    )
    (net (code "97") (name "/PF1") (class "Default")
      (node (ref "U14") (pin "11") (pinfunction "PF1/PH1_11") (pintype "passive"))
    )
    (net (code "98") (name "/PF2") (class "Default")
      (node (ref "U14") (pin "12") (pinfunction "PF2_12") (pintype "passive"))
    )
    (net (code "99") (name "/PF3") (class "Default")
      (node (ref "U14") (pin "13") (pinfunction "PF3_13") (pintype "passive"))
    )
    (net (code "100") (name "/PF4") (class "Default")
      (node (ref "U14") (pin "14") (pinfunction "PF4_14") (pintype "passive"))
    )
    (net (code "101") (name "/PF5") (class "Default")
      (node (ref "U14") (pin "15") (pinfunction "PF5_15") (pintype "passive"))
    )
    (net (code "102") (name "/PF6") (class "Default")
      (node (ref "U14") (pin "18") (pinfunction "PF6_18") (pintype "passive"))
    )
    (net (code "103") (name "/PF7") (class "Default")
      (node (ref "U14") (pin "19") (pinfunction "PF7_19") (pintype "passive"))
    )
    (net (code "104") (name "/PF8") (class "Default")
      (node (ref "U14") (pin "20") (pinfunction "PF8_20") (pintype "passive"))
    )
    (net (code "105") (name "/PF9") (class "Default")
      (node (ref "U14") (pin "21") (pinfunction "PF9_21") (pintype "passive"))
    )
    (net (code "106") (name "/PF10") (class "Default")
      (node (ref "U14") (pin "22") (pinfunction "PF10_22") (pintype "passive"))
    )
    (net (code "107") (name "/PF11") (class "Default")
      (node (ref "U14") (pin "49") (pinfunction "PF11_49") (pintype "passive"))
    )
    (net (code "108") (name "/PF12") (class "Default")
      (node (ref "U14") (pin "50") (pinfunction "PF12_50") (pintype "passive"))
    )
    (net (code "109") (name "/PF13") (class "Default")
      (node (ref "U14") (pin "53") (pinfunction "PF13_53") (pintype "passive"))
    )
    (net (code "110") (name "/PF14") (class "Default")
      (node (ref "U14") (pin "54") (pinfunction "PF14_54") (pintype "passive"))
    )
    (net (code "111") (name "/PF15") (class "Default")
      (node (ref "U14") (pin "55") (pinfunction "PF15_55") (pintype "passive"))
    )
    (net (code "113") (name "/PG0") (class "Default")
      (node (ref "U14") (pin "56") (pinfunction "PG0_56") (pintype "passive"))
    )
    (net (code "114") (name "/PG1") (class "Default")
      (node (ref "U14") (pin "57") (pinfunction "PG1_57") (pintype "passive"))
    )
    (net (code "115") (name "/PG2") (class "Default")
      (node (ref "U14") (pin "87") (pinfunction "PG2_87") (pintype "passive"))
    )
    (net (code "116") (name "/PG3") (class "Default")
      (node (ref "U14") (pin "88") (pinfunction "PG3_88") (pintype "passive"))
    )
    (net (code "117") (name "/PG4") (class "Default")
      (node (ref "U14") (pin "89") (pinfunction "PG4_89") (pintype "passive"))
    )
    (net (code "118") (name "/PG5") (class "Default")
      (node (ref "U14") (pin "90") (pinfunction "PG5_90") (pintype "passive"))
    )
    (net (code "119") (name "/PG6") (class "Default")
      (node (ref "U14") (pin "91") (pinfunction "PG6_91") (pintype "passive"))
    )
    (net (code "120") (name "/PG7") (class "Default")
      (node (ref "SB74") (pin "2") (pinfunction "2_2") (pintype "passive"))
      (node (ref "U14") (pin "92") (pinfunction "PG7_92") (pintype "passive"))
    )
    (net (code "121") (name "/PG8") (class "Default")
      (node (ref "U14") (pin "93") (pinfunction "PG8_93") (pintype "passive"))
    )
    (net (code "122") (name "/PG9") (class "Default")
      (node (ref "U14") (pin "124") (pinfunction "PG9_124") (pintype "passive"))
    )
    (net (code "123") (name "/PG10") (class "Default")
      (node (ref "U14") (pin "125") (pinfunction "PG10_125") (pintype "passive"))
    )
    (net (code "124") (name "/PG11") (class "Default")
      (node (ref "SB34") (pin "2") (pinfunction "2_2") (pintype "passive"))
      (node (ref "U14") (pin "126") (pinfunction "PG11_126") (pintype "passive"))
    )
    (net (code "125") (name "/PG12") (class "Default")
      (node (ref "U14") (pin "127") (pinfunction "PG12_127") (pintype "passive"))
    )
    (net (code "126") (name "/PG13") (class "Default")
      (node (ref "SB37") (pin "2") (pinfunction "2_2") (pintype "passive"))
      (node (ref "U14") (pin "128") (pinfunction "PG13_128") (pintype "passive"))
    )
    (net (code "127") (name "/PG14") (class "Default")
      (node (ref "U14") (pin "129") (pinfunction "PG14_129") (pintype "passive"))
    )
    (net (code "128") (name "/PG15") (class "Default")
      (node (ref "U14") (pin "132") (pinfunction "PG15_132") (pintype "passive"))
    )
    (net (code "130") (name "/PH0") (class "Default")
      (node (ref "SB50") (pin "2") (pinfunction "2_2") (pintype "passive"))
    )
    (net (code "131") (name "/PH0-OSC_IN") (class "Default")
      (node (ref "SB3") (pin "1") (pinfunction "1_1") (pintype "passive"))
      (node (ref "SB49") (pin "1") (pinfunction "1_1") (pintype "passive"))
      (node (ref "SB50") (pin "1") (pinfunction "1_1") (pintype "passive"))
      (node (ref "U14") (pin "23") (pinfunction "PH0-OSC_IN_23") (pintype "passive"))
    )
    (net (code "132") (name "/PH1") (class "Default")
      (node (ref "SB48") (pin "2") (pinfunction "2_2") (pintype "passive"))
    )
    (net (code "133") (name "/PH1-OSC_OUT") (class "Default")
      (node (ref "SB4") (pin "1") (pinfunction "1_1") (pintype "passive"))
      (node (ref "SB48") (pin "1") (pinfunction "1_1") (pintype "passive"))
      (node (ref "U14") (pin "24") (pinfunction "PH1-OSC_OUT_24") (pintype "passive"))
    )
    (net (code "135") (name "/RMII_CRS_DV") (class "Default")
      (node (ref "SB38") (pin "2") (pinfunction "2_2") (pintype "passive"))
    )
    (net (code "136") (name "/RMII_MDC") (class "Default")
      (node (ref "SB62") (pin "1") (pinfunction "1_1") (pintype "passive"))
    )
    (net (code "137") (name "/RMII_MDIO") (class "Default")
      (node (ref "SB69") (pin "2") (pinfunction "2_2") (pintype "passive"))
    )
    (net (code "138") (name "/RMII_REF_CLK") (class "Default")
      (node (ref "SB58") (pin "2") (pinfunction "2_2") (pintype "passive"))
    )
    (net (code "139") (name "/RMII_RXD0") (class "Default")
      (node (ref "SB42") (pin "1") (pinfunction "1_1") (pintype "passive"))
    )
    (net (code "140") (name "/RMII_RXD1") (class "Default")
      (node (ref "SB36") (pin "1") (pinfunction "1_1") (pintype "passive"))
    )
    (net (code "141") (name "/RMII_TXD0") (class "Default")
      (node (ref "SB37") (pin "1") (pinfunction "1_1") (pintype "passive"))
    )
    (net (code "142") (name "/RMII_TXD1") (class "Default")
      (node (ref "JP6") (pin "2") (pinfunction "NO_2") (pintype "passive"))
    )
    (net (code "143") (name "/RMII_TX_EN") (class "Default")
      (node (ref "SB34") (pin "1") (pinfunction "1_1") (pintype "passive"))
    )
    (net (code "144") (name "/STLK_MCO") (class "Default")
      (node (ref "SB49") (pin "2") (pinfunction "2_2") (pintype "passive"))
    )
    (net (code "145") (name "/SWO") (class "Default")
      (node (ref "SB39") (pin "1") (pinfunction "1_1") (pintype "passive"))
    )
    (net (code "146") (name "/TRACE_CK") (class "Default")
      (node (ref "SB79") (pin "2") (pinfunction "2_2") (pintype "passive"))
    )
    (net (code "147") (name "/TRACE_D0") (class "Default")
      (node (ref "SB80") (pin "2") (pinfunction "2_2") (pintype "passive"))
    )
    (net (code "148") (name "/TRACE_D1") (class "Default")
      (node (ref "SB81") (pin "2") (pinfunction "2_2") (pintype "passive"))
    )
    (net (code "149") (name "/TRACE_D2") (class "Default")
      (node (ref "SB82") (pin "2") (pinfunction "2_2") (pintype "passive"))
    )
    (net (code "150") (name "/TRACE_D3") (class "Default")
      (node (ref "SB83") (pin "2") (pinfunction "2_2") (pintype "passive"))
    )
    (net (code "151") (name "/T_VCP_RX") (class "Default")
      (node (ref "SB18") (pin "2") (pinfunction "2_2") (pintype "passive"))
      (node (ref "SB40") (pin "1") (pinfunction "1_1") (pintype "passive"))
    )
    (net (code "152") (name "/T_VCP_TX") (class "Default")
      (node (ref "SB15") (pin "1") (pinfunction "1_1") (pintype "passive"))
      (node (ref "SB24") (pin "2") (pinfunction "2_2") (pintype "passive"))
    )
    (net (code "153") (name "/UCPD_CC1") (class "Default")
      (node (ref "SB29") (pin "2") (pinfunction "2_2") (pintype "passive"))
    )
    (net (code "154") (name "/UCPD_CC2") (class "Default")
      (node (ref "SB30") (pin "2") (pinfunction "2_2") (pintype "passive"))
    )
    (net (code "155") (name "/UCPD_DBn") (class "Default")
      (node (ref "SB31") (pin "1") (pinfunction "1_1") (pintype "passive"))
    )
    (net (code "156") (name "/UCPD_FLT") (class "Default")
      (node (ref "SB74") (pin "1") (pinfunction "1_1") (pintype "passive"))
    )
    (net (code "157") (name "/USB_FS_N") (class "Default")
      (node (ref "SB27") (pin "2") (pinfunction "2_2") (pintype "passive"))
    )
    (net (code "158") (name "/USB_FS_P") (class "Default")
      (node (ref "SB28") (pin "2") (pinfunction "2_2") (pintype "passive"))
    )
    (net (code "159") (name "/VBUS_SENSE") (class "Default")
      (node (ref "SB56") (pin "1") (pinfunction "1_1") (pintype "passive"))
    )
    (net (code "160") (name "/WAKEUP_KEY") (class "Default")
      (node (ref "B1") (pin "3") (pinfunction "3_3") (pintype "passive"))
      (node (ref "B1") (pin "4") (pinfunction "4_4") (pintype "passive"))
      (node (ref "R62") (pin "2") (pinfunction "2_2") (pintype "passive"))
      (node (ref "R71") (pin "2") (pinfunction "2_2") (pintype "passive"))
      (node (ref "U22") (pin "1") (pinfunction "IO1_1") (pintype "passive"))
    )
    (net (code "161") (name "GND") (class "Default")
      (node (ref "B2") (pin "3") (pinfunction "3_3") (pintype "passive"))
      (node (ref "B2") (pin "4") (pinfunction "4_4") (pintype "passive"))
      (node (ref "C59") (pin "1") (pinfunction "1_1") (pintype "passive"))
      (node (ref "C69") (pin "1") (pinfunction "1_1") (pintype "passive"))
      (node (ref "C70") (pin "2") (pinfunction "2_2") (pintype "passive"))
      (node (ref "C71") (pin "2") (pinfunction "2_2") (pintype "passive"))
      (node (ref "C72") (pin "2") (pinfunction "2_2") (pintype "passive"))
      (node (ref "C73") (pin "2") (pinfunction "2_2") (pintype "passive"))
      (node (ref "R31") (pin "2") (pinfunction "2_2") (pintype "passive"))
      (node (ref "R62") (pin "1") (pinfunction "1_1") (pintype "passive"))
      (node (ref "U21") (pin "2") (pinfunction "GND_2") (pintype "passive"))
      (node (ref "U22") (pin "2") (pinfunction "GND_2") (pintype "passive"))
      (node (ref "X3") (pin "2") (pinfunction "2_2") (pintype "passive"))
      (node (ref "X3") (pin "4") (pinfunction "4_4") (pintype "passive"))
    )
    (net (code "162") (name "Net-(C69-Pad2)") (class "Default")
      (node (ref "C69") (pin "2") (pinfunction "2_2") (pintype "passive"))
      (node (ref "R71") (pin "1") (pinfunction "1_1") (pintype "passive"))
      (node (ref "SB54") (pin "2") (pinfunction "2_2") (pintype "passive"))
      (node (ref "SB59") (pin "1") (pinfunction "1_1") (pintype "passive"))
    )
    (net (code "163") (name "VDD") (class "Default")
      (node (ref "B1") (pin "1") (pinfunction "1_1") (pintype "passive"))
      (node (ref "B1") (pin "2") (pinfunction "2_2") (pintype "passive"))
    )
  )
)
